# sensors.net
KiCad netlist of a schematic drawn in Altium Designer
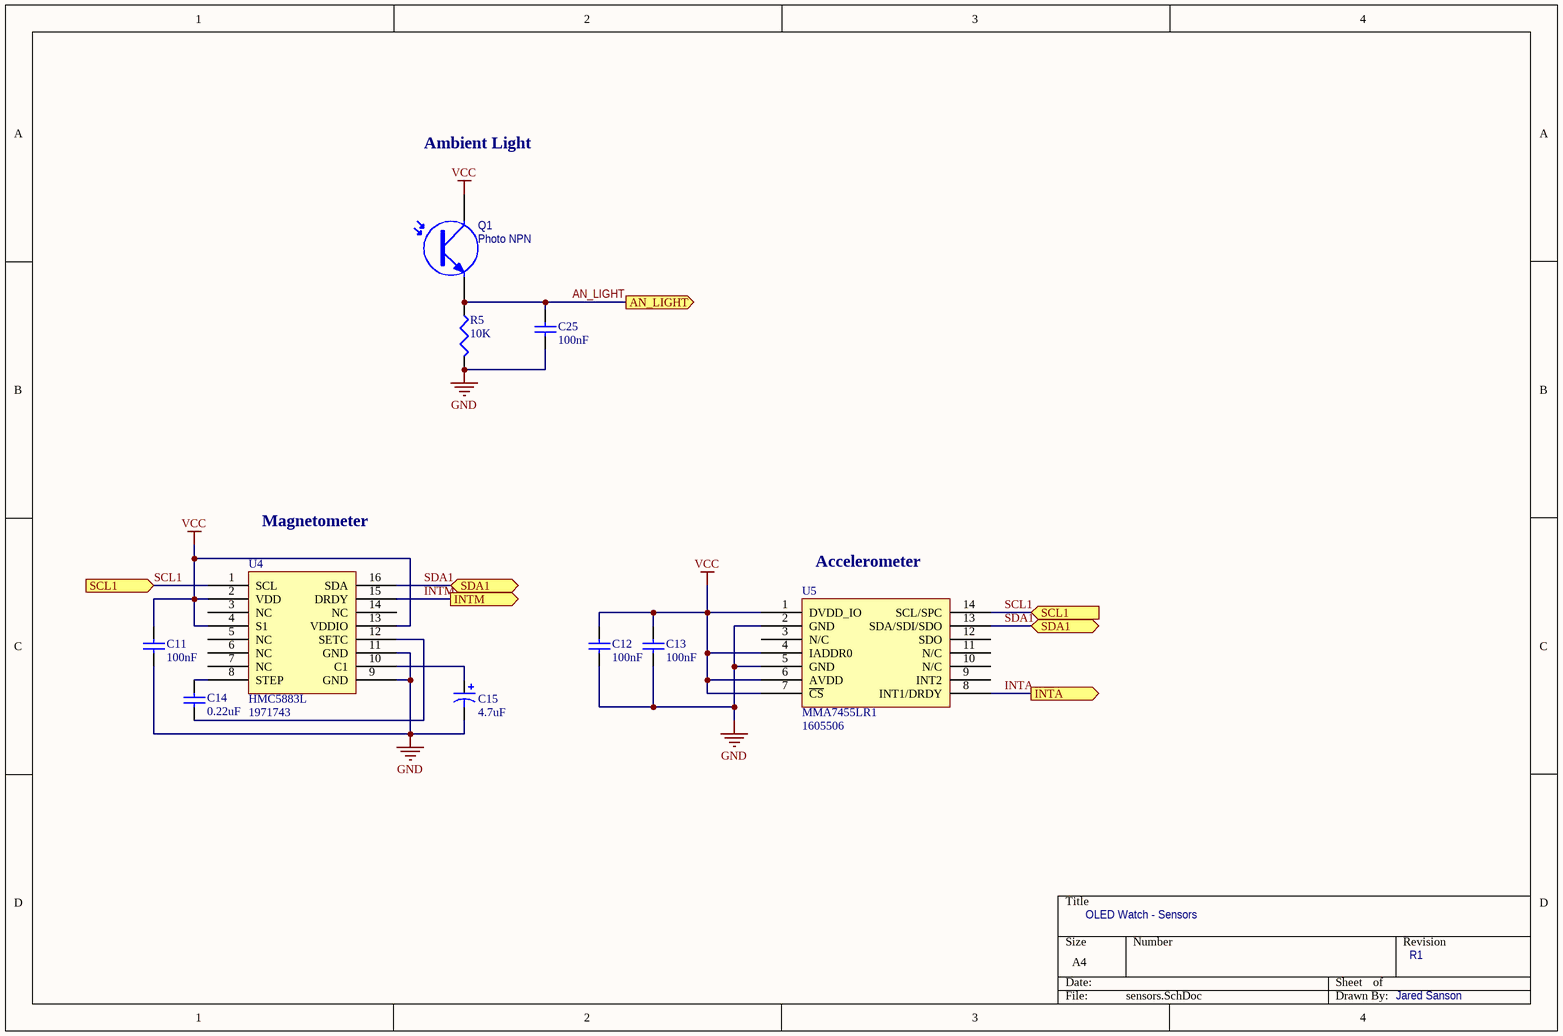
[diagram p0: sensors.SchDoc]

(export (version "E")
  (design (tool "Eeschema 10.0.6"))
  (components
    (comp (ref "C11")
      (value "100nF")
      (footprint "0603C")
      (description "Capacitor")
      (fields (field (name "Comment") "Cap") (field (name "PUBLISHER") "Altium Limited"))
      (libsource (lib "Miscellaneous Devices") (part "Cap"))
    )
    (comp (ref "C12")
      (value "100nF")
      (footprint "0603C")
      (description "Capacitor")
      (fields (field (name "Comment") "Cap") (field (name "PUBLISHER") "Altium Limited"))
      (libsource (lib "Miscellaneous Devices") (part "Cap"))
    )
    (comp (ref "C13")
      (value "100nF")
      (footprint "0603C")
      (description "Capacitor")
      (fields (field (name "Comment") "Cap") (field (name "PUBLISHER") "Altium Limited"))
      (libsource (lib "Miscellaneous Devices") (part "Cap"))
    )
    (comp (ref "C14")
      (value "0.22uF")
      (footprint "0603C")
      (description "Capacitor")
      (fields (field (name "Comment") "Cap") (field (name "PUBLISHER") "Altium Limited"))
      (libsource (lib "Miscellaneous Devices") (part "Cap"))
    )
    (comp (ref "C15")
      (value "4.7uF")
      (footprint "0805C")
      (description "Polarized Capacitor (Radial)")
      (fields (field (name "Comment") "Cap Pol1") (field (name "PUBLISHER") "Altium Limited"))
      (libsource (lib "Miscellaneous Devices") (part "Cap Pol1"))
    )
    (comp (ref "C25")
      (value "100nF")
      (footprint "0603C")
      (description "Capacitor")
      (fields (field (name "Comment") "Cap") (field (name "PUBLISHER") "Altium Limited"))
      (libsource (lib "Miscellaneous Devices") (part "Cap"))
    )
    (comp (ref "Q1")
      (value "Photo NPN")
      (footprint "TEMT6000")
      (description "NPN Phototransistor")
      (fields (field (name "PUBLISHER") "Altium Limited"))
      (libsource (lib "Miscellaneous Devices") (part "Photo NPN"))
    )
    (comp (ref "R5")
      (value "10K")
      (footprint "0603R")
      (description "Resistor")
      (fields (field (name "Comment") "Res3") (field (name "PUBLISHER") "Altium Limited"))
      (libsource (lib "Miscellaneous Devices") (part "Res3"))
    )
    (comp (ref "U4")
      (value "HMC5883L")
      (footprint "HMC5883L_16PINQFN")
      (description "Honeywell 3 Axis Magnetometer")
      (fields
        (field (name "SUPPLIER PART NUMBER 1") "1971743")
        (field (name "MANUFACTURER") "HONEYWELL M&PS")
        (field (name "MANUFACTURER PART NUMBER") "HMC5883L-TR")
      )
      (libsource (lib "JLib") (part "HMC5883L"))
    )
    (comp (ref "U5")
      (value "MMA7455LR1")
      (footprint "LGA80P500X300-14N")
      (description "FREESCALE SEMICONDUCTOR - MMA7455LR1 - IC, 3-AXIS DIGITAL 2, 4, 8G, 14-LGA")
      (fields
        (field (name "SUPPLIER PART NUMBER 1") "1605506")
        (field (name "MANUFACTURER") "FREESCALE SEMICONDUCTOR")
      )
      (libsource (lib "JLib") (part "MMA7455LR1"))
    )
  )
  (nets
    (net (code "1") (name "/AN_LIGHT") (class "Default")
      (node (ref "C25") (pin "1") (pinfunction "1_1") (pintype "passive"))
      (node (ref "Q1") (pin "3") (pinfunction "E_3") (pintype "passive"))
      (node (ref "R5") (pin "1") (pinfunction "1_1") (pintype "passive"))
    )
    (net (code "2") (name "/INTA") (class "Default")
      (node (ref "U5") (pin "8") (pinfunction "INT1/DRDY_8") (pintype "passive"))
    )
    (net (code "3") (name "/INTM") (class "Default")
      (node (ref "U4") (pin "15") (pinfunction "DRDY_15") (pintype "passive"))
    )
    (net (code "4") (name "/SCL1") (class "Default")
      (node (ref "U4") (pin "1") (pinfunction "SCL_1") (pintype "passive"))
      (node (ref "U5") (pin "14") (pinfunction "SCL/SPC_14") (pintype "passive"))
    )
    (net (code "5") (name "/SDA1") (class "Default")
      (node (ref "U4") (pin "16") (pinfunction "SDA_16") (pintype "passive"))
      (node (ref "U5") (pin "13") (pinfunction "SDA/SDI/SDO_13") (pintype "passive"))
    )
    (net (code "6") (name "GND") (class "Default")
      (node (ref "C11") (pin "2") (pinfunction "2_2") (pintype "passive"))
      (node (ref "C12") (pin "2") (pinfunction "2_2") (pintype "passive"))
      (node (ref "C13") (pin "2") (pinfunction "2_2") (pintype "passive"))
      (node (ref "C15") (pin "2") (pinfunction "2_2") (pintype "passive"))
      (node (ref "C25") (pin "2") (pinfunction "2_2") (pintype "passive"))
      (node (ref "R5") (pin "2") (pinfunction "2_2") (pintype "passive"))
      (node (ref "U4") (pin "11") (pinfunction "GND_11") (pintype "passive"))
      (node (ref "U4") (pin "9") (pinfunction "GND_9") (pintype "passive"))
      (node (ref "U5") (pin "2") (pinfunction "GND_2") (pintype "passive"))
      (node (ref "U5") (pin "5") (pinfunction "GND_5") (pintype "passive"))
    )
    (net (code "7") (name "Net-(U4-C1)") (class "Default")
      (node (ref "C15") (pin "1") (pinfunction "1_1") (pintype "passive"))
      (node (ref "U4") (pin "10") (pinfunction "C1_10") (pintype "passive"))
    )
    (net (code "8") (name "Net-(U4-SETC)") (class "Default")
      (node (ref "C14") (pin "1") (pinfunction "1_1") (pintype "passive"))
      (node (ref "U4") (pin "12") (pinfunction "SETC_12") (pintype "passive"))
    )
    (net (code "9") (name "Net-(U4-STEP)") (class "Default")
      (node (ref "C14") (pin "2") (pinfunction "2_2") (pintype "passive"))
      (node (ref "U4") (pin "8") (pinfunction "STEP_8") (pintype "passive"))
    )
    (net (code "10") (name "VCC") (class "Default")
      (node (ref "C11") (pin "1") (pinfunction "1_1") (pintype "passive"))
      (node (ref "C12") (pin "1") (pinfunction "1_1") (pintype "passive"))
      (node (ref "C13") (pin "1") (pinfunction "1_1") (pintype "passive"))
      (node (ref "Q1") (pin "1") (pinfunction "C_1") (pintype "passive"))
      (node (ref "U4") (pin "13") (pinfunction "VDDIO_13") (pintype "passive"))
      (node (ref "U4") (pin "2") (pinfunction "VDD_2") (pintype "passive"))
      (node (ref "U4") (pin "4") (pinfunction "S1_4") (pintype "passive"))
      (node (ref "U5") (pin "1") (pinfunction "DVDD_IO_1") (pintype "passive"))
      (node (ref "U5") (pin "4") (pinfunction "IADDR0_4") (pintype "passive"))
      (node (ref "U5") (pin "6") (pinfunction "AVDD_6") (pintype "passive"))
      (node (ref "U5") (pin "7") (pinfunction "~{CS}_7") (pintype "passive"))
    )
    (net (code "11") (name "unconnected-(U4-NC-Pad3)") (class "Default")
      (node (ref "U4") (pin "3") (pinfunction "NC_3") (pintype "passive"))
    )
    (net (code "12") (name "unconnected-(U4-NC-Pad5)") (class "Default")
      (node (ref "U4") (pin "5") (pinfunction "NC_5") (pintype "passive"))
    )
    (net (code "13") (name "unconnected-(U4-NC-Pad6)") (class "Default")
      (node (ref "U4") (pin "6") (pinfunction "NC_6") (pintype "passive"))
    )
    (net (code "14") (name "unconnected-(U4-NC-Pad7)") (class "Default")
      (node (ref "U4") (pin "7") (pinfunction "NC_7") (pintype "passive"))
    )
    (net (code "15") (name "unconnected-(U4-NC-Pad14)") (class "Default")
      (node (ref "U4") (pin "14") (pinfunction "NC_14") (pintype "passive"))
    )
    (net (code "16") (name "unconnected-(U5-INT2-Pad9)") (class "Default")
      (node (ref "U5") (pin "9") (pinfunction "INT2_9") (pintype "passive"))
    )
    (net (code "17") (name "unconnected-(U5-N{slash}C-Pad3)") (class "Default")
      (node (ref "U5") (pin "3") (pinfunction "N/C_3") (pintype "passive"))
    )
    (net (code "18") (name "unconnected-(U5-N{slash}C-Pad10)") (class "Default")
      (node (ref "U5") (pin "10") (pinfunction "N/C_10") (pintype "passive"))
    )
    (net (code "19") (name "unconnected-(U5-N{slash}C-Pad11)") (class "Default")
      (node (ref "U5") (pin "11") (pinfunction "N/C_11") (pintype "passive"))
    )
    (net (code "20") (name "unconnected-(U5-SDO-Pad12)") (class "Default")
      (node (ref "U5") (pin "12") (pinfunction "SDO_12") (pintype "passive"))
    )
  )
)
